# button_board.net
KiCad netlist of a schematic drawn in EAGLE
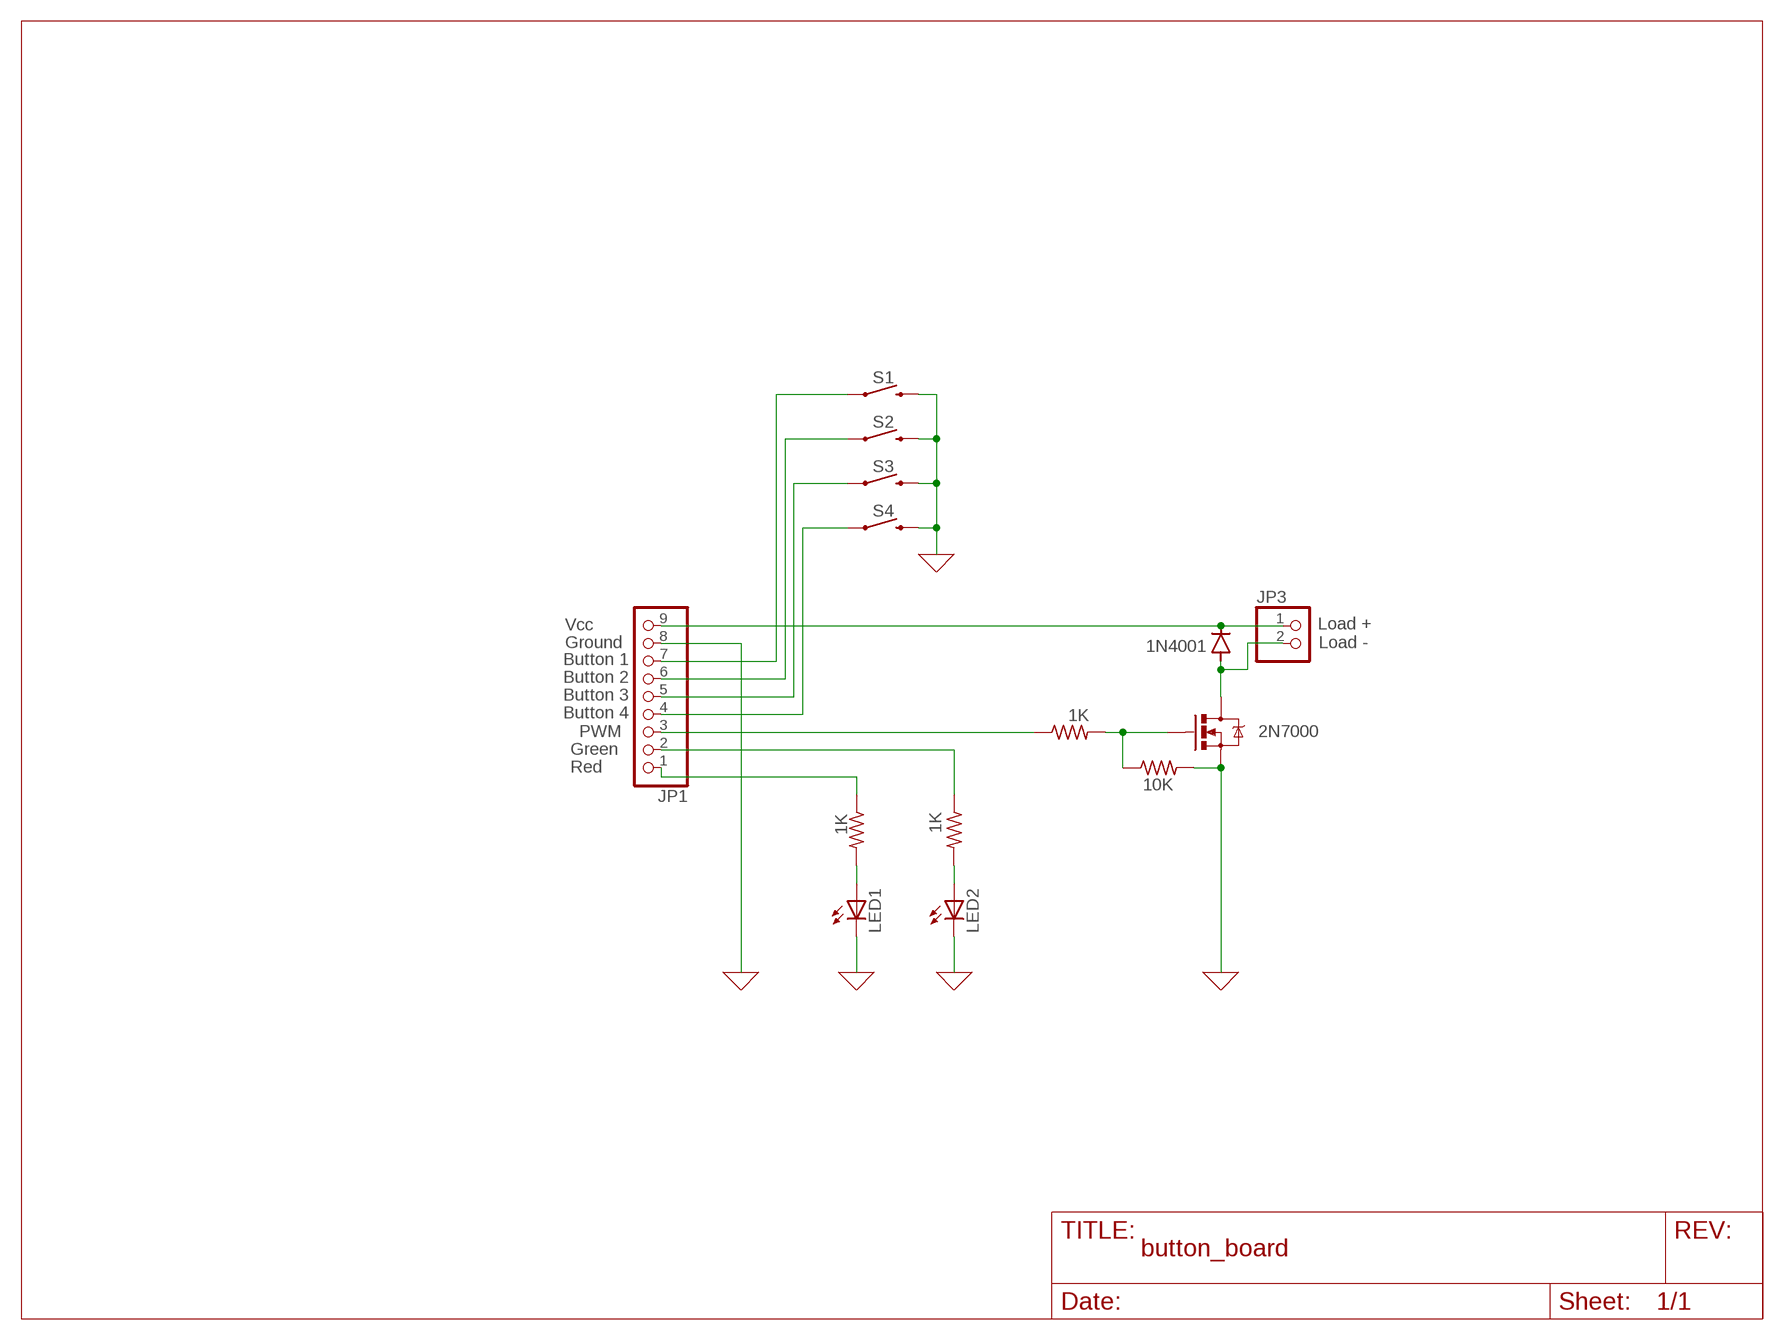
[diagram p0: schematic, sheet 1]

(export (version "E")
  (design (tool "Eeschema 10.0.6"))
  (components
    (comp (ref "D1")
      (value "1N4001")
      (footprint "eagle-import:DO-41")
      (fields
        (field (name "DIGIKEY_PART_NUMBER") "1N4004MSCT-ND")
        (field (name "MANUFACTURER") "Micro Commercial Co")
        (field (name "MPN") "1N4004")
        (field (name "CREATED_BY") "PCBLayout.com")
      )
      (libsource (lib "eagle-import") (part "1N4004"))
    )
    (comp (ref "JP1")
      (value "PINHD-1X9")
      (footprint "eagle-import:1X09")
      (libsource (lib "eagle-import") (part "PINHD-1X9"))
    )
    (comp (ref "JP3")
      (value "PINHD-1X2")
      (footprint "eagle-import:1X02")
      (libsource (lib "eagle-import") (part "PINHD-1X2"))
    )
    (comp (ref "LED1")
      (value "LED5MM")
      (footprint "eagle-import:LED5MM")
      (libsource (lib "eagle-import") (part "LED5MM"))
    )
    (comp (ref "LED2")
      (value "LED5MM")
      (footprint "eagle-import:LED5MM")
      (libsource (lib "eagle-import") (part "LED5MM"))
    )
    (comp (ref "Q1")
      (value "MOSFET-NCHANNEL2N7000")
      (footprint "eagle-import:TO-92")
      (libsource (lib "eagle-import") (part "MOSFET-NCHANNEL2N7000"))
    )
    (comp (ref "R1")
      (value "1K")
      (footprint "eagle-import:0207_10")
      (libsource (lib "eagle-import") (part "R-US_0207/10"))
    )
    (comp (ref "R2")
      (value "10K")
      (footprint "eagle-import:0207_10")
      (libsource (lib "eagle-import") (part "R-US_0207/10"))
    )
    (comp (ref "R3")
      (value "1K")
      (footprint "eagle-import:0207_10")
      (libsource (lib "eagle-import") (part "R-US_0207/10"))
    )
    (comp (ref "R4")
      (value "1K")
      (footprint "eagle-import:0207_10")
      (libsource (lib "eagle-import") (part "R-US_0207/10"))
    )
    (comp (ref "S1")
      (value "MOMENTARY-SWITCH-SPST-PTH-6.0MM")
      (footprint "eagle-import:TACTILE_SWITCH_PTH_6.0MM")
      (libsource (lib "eagle-import") (part "MOMENTARY-SWITCH-SPST-PTH-6.0MM"))
    )
    (comp (ref "S2")
      (value "MOMENTARY-SWITCH-SPST-PTH-6.0MM")
      (footprint "eagle-import:TACTILE_SWITCH_PTH_6.0MM")
      (libsource (lib "eagle-import") (part "MOMENTARY-SWITCH-SPST-PTH-6.0MM"))
    )
    (comp (ref "S3")
      (value "MOMENTARY-SWITCH-SPST-PTH-6.0MM")
      (footprint "eagle-import:TACTILE_SWITCH_PTH_6.0MM")
      (libsource (lib "eagle-import") (part "MOMENTARY-SWITCH-SPST-PTH-6.0MM"))
    )
    (comp (ref "S4")
      (value "MOMENTARY-SWITCH-SPST-PTH-6.0MM")
      (footprint "eagle-import:TACTILE_SWITCH_PTH_6.0MM")
      (libsource (lib "eagle-import") (part "MOMENTARY-SWITCH-SPST-PTH-6.0MM"))
    )
  )
  (nets
    (net (code "1") (name "GND") (class "Default")
      (node (ref "JP1") (pin "8") (pinfunction "8_8") (pintype "passive"))
      (node (ref "LED1") (pin "K") (pinfunction "C_K") (pintype "passive"))
      (node (ref "LED2") (pin "K") (pinfunction "C_K") (pintype "passive"))
      (node (ref "Q1") (pin "1") (pinfunction "S_1") (pintype "passive"))
      (node (ref "R2") (pin "2") (pinfunction "2_2") (pintype "passive"))
      (node (ref "S1") (pin "3") (pinfunction "2_3") (pintype "passive"))
      (node (ref "S2") (pin "3") (pinfunction "2_3") (pintype "passive"))
      (node (ref "S3") (pin "3") (pinfunction "2_3") (pintype "passive"))
      (node (ref "S4") (pin "3") (pinfunction "2_3") (pintype "passive"))
    )
    (net (code "2") (name "Net-(D1-PadC)") (class "Default")
      (node (ref "D1") (pin "C") (pinfunction "C_C") (pintype "passive"))
      (node (ref "JP1") (pin "9") (pinfunction "9_9") (pintype "passive"))
      (node (ref "JP3") (pin "1") (pinfunction "1_1") (pintype "passive"))
    )
    (net (code "3") (name "Net-(JP1-Pad1)") (class "Default")
      (node (ref "JP1") (pin "1") (pinfunction "1_1") (pintype "passive"))
      (node (ref "R3") (pin "1") (pinfunction "1_1") (pintype "passive"))
    )
    (net (code "4") (name "Net-(JP1-Pad2)") (class "Default")
      (node (ref "JP1") (pin "2") (pinfunction "2_2") (pintype "passive"))
      (node (ref "R4") (pin "1") (pinfunction "1_1") (pintype "passive"))
    )
    (net (code "5") (name "Net-(JP1-Pad3)") (class "Default")
      (node (ref "JP1") (pin "3") (pinfunction "3_3") (pintype "passive"))
      (node (ref "R1") (pin "1") (pinfunction "1_1") (pintype "passive"))
    )
    (net (code "6") (name "Net-(JP1-Pad4)") (class "Default")
      (node (ref "JP1") (pin "4") (pinfunction "4_4") (pintype "passive"))
      (node (ref "S4") (pin "1") (pinfunction "1_1") (pintype "passive"))
    )
    (net (code "7") (name "Net-(JP1-Pad5)") (class "Default")
      (node (ref "JP1") (pin "5") (pinfunction "5_5") (pintype "passive"))
      (node (ref "S3") (pin "1") (pinfunction "1_1") (pintype "passive"))
    )
    (net (code "8") (name "Net-(JP1-Pad6)") (class "Default")
      (node (ref "JP1") (pin "6") (pinfunction "6_6") (pintype "passive"))
      (node (ref "S2") (pin "1") (pinfunction "1_1") (pintype "passive"))
    )
    (net (code "9") (name "Net-(JP1-Pad7)") (class "Default")
      (node (ref "JP1") (pin "7") (pinfunction "7_7") (pintype "passive"))
      (node (ref "S1") (pin "1") (pinfunction "1_1") (pintype "passive"))
    )
    (net (code "10") (name "Net-(LED1-PadA)") (class "Default")
      (node (ref "LED1") (pin "A") (pinfunction "A_A") (pintype "passive"))
      (node (ref "R3") (pin "2") (pinfunction "2_2") (pintype "passive"))
    )
    (net (code "11") (name "Net-(LED2-PadA)") (class "Default")
      (node (ref "LED2") (pin "A") (pinfunction "A_A") (pintype "passive"))
      (node (ref "R4") (pin "2") (pinfunction "2_2") (pintype "passive"))
    )
    (net (code "12") (name "Net-(Q1-D)") (class "Default")
      (node (ref "D1") (pin "A") (pinfunction "A_A") (pintype "passive"))
      (node (ref "JP3") (pin "2") (pinfunction "2_2") (pintype "passive"))
      (node (ref "Q1") (pin "3") (pinfunction "D_3") (pintype "passive"))
    )
    (net (code "13") (name "Net-(Q1-G)") (class "Default")
      (node (ref "Q1") (pin "2") (pinfunction "G_2") (pintype "passive"))
      (node (ref "R1") (pin "2") (pinfunction "2_2") (pintype "passive"))
      (node (ref "R2") (pin "1") (pinfunction "1_1") (pintype "passive"))
    )
  )
)
